# SparkFun_MicroMod_Function_SARA-R5.net
KiCad netlist of a schematic drawn in EAGLE
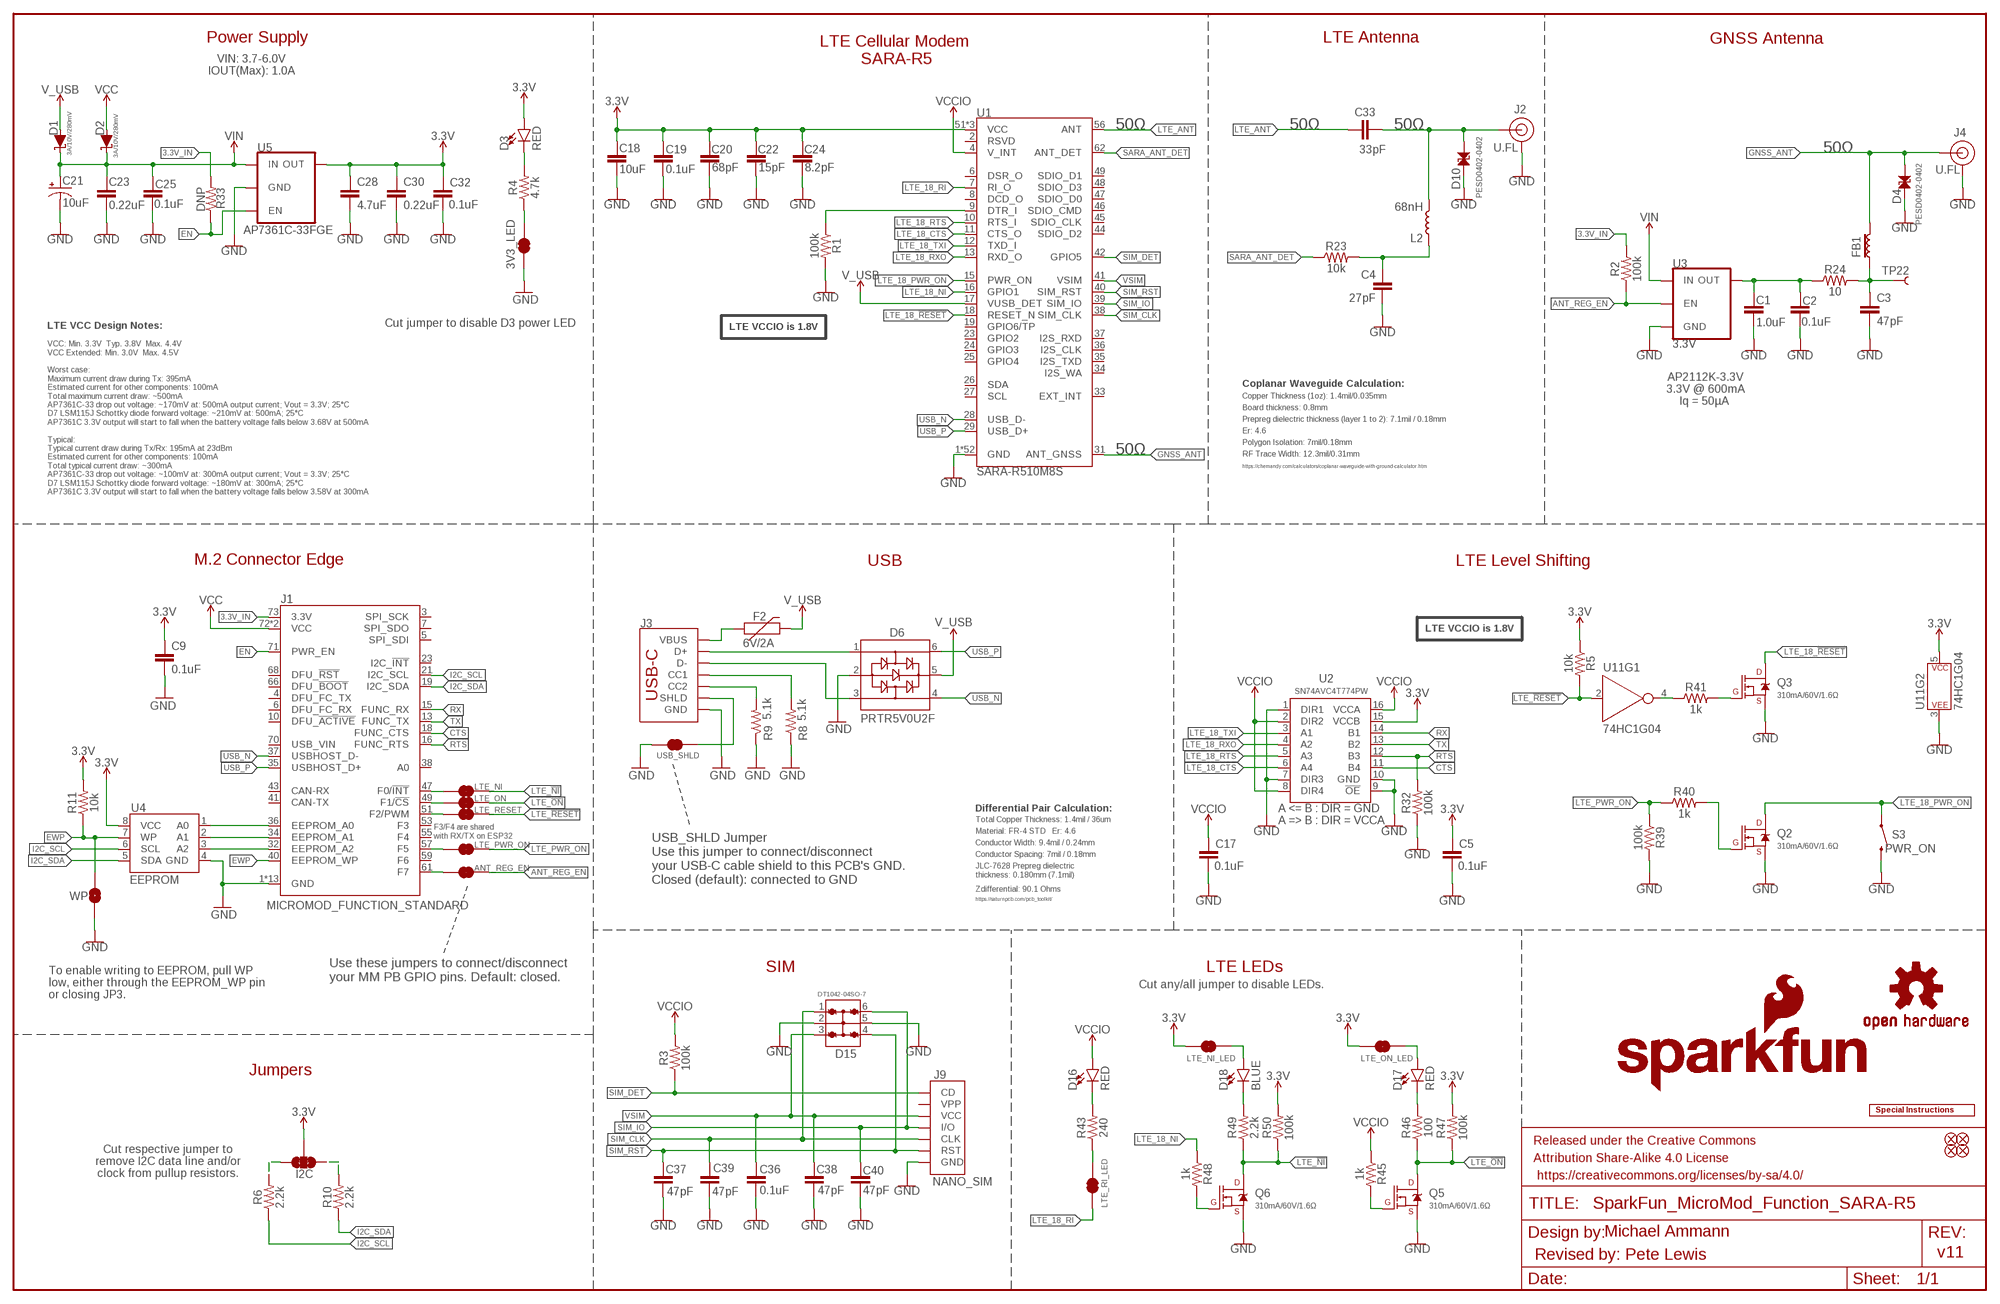
[diagram p0: schematic, sheet 1]

(export (version "E")
  (design (tool "Eeschema 10.0.6"))
  (components
    (comp (ref "3V3_LED")
      (value "JUMPER-SMT_2_NC_TRACE_SILK")
      (footprint "eagle-import:SMT-JUMPER_2_NC_TRACE_SILK")
      (libsource (lib "eagle-import") (part "JUMPER-SMT_2_NC_TRACE_SILK"))
    )
    (comp (ref "ANT_REG_EN")
      (value "JUMPER-SMT_2_NC_TRACE_SILK")
      (footprint "eagle-import:SMT-JUMPER_2_NC_TRACE_SILK")
      (libsource (lib "eagle-import") (part "JUMPER-SMT_2_NC_TRACE_SILK"))
    )
    (comp (ref "C1")
      (value "1.0uF")
      (footprint "eagle-import:0603")
      (libsource (lib "eagle-import") (part "1.0UF-0603-16V-10%"))
    )
    (comp (ref "C2")
      (value "0.1uF")
      (footprint "eagle-import:0402-TIGHT")
      (libsource (lib "eagle-import") (part "0.1UF-0402T-16V-10%"))
    )
    (comp (ref "C3")
      (value "47pF")
      (footprint "eagle-import:0603")
      (libsource (lib "eagle-import") (part "47PF-0603-50V-5%"))
    )
    (comp (ref "C4")
      (value "27pF")
      (footprint "eagle-import:0402")
      (libsource (lib "eagle-import") (part "27PF-0402-50V-5%"))
    )
    (comp (ref "C5")
      (value "0.1uF")
      (footprint "eagle-import:0402-TIGHT")
      (libsource (lib "eagle-import") (part "0.1UF-0402T-16V-10%"))
    )
    (comp (ref "C9")
      (value "0.1uF")
      (footprint "eagle-import:0402-TIGHT")
      (libsource (lib "eagle-import") (part "0.1UF-0402T-16V-10%"))
    )
    (comp (ref "C17")
      (value "0.1uF")
      (footprint "eagle-import:0402-TIGHT")
      (libsource (lib "eagle-import") (part "0.1UF-0402T-16V-10%"))
    )
    (comp (ref "C18")
      (value "10uF")
      (footprint "eagle-import:0603")
      (libsource (lib "eagle-import") (part "10UF-0603-6.3V-20%"))
    )
    (comp (ref "C19")
      (value "0.1uF")
      (footprint "eagle-import:0402-TIGHT")
      (libsource (lib "eagle-import") (part "0.1UF-0402T-16V-10%"))
    )
    (comp (ref "C20")
      (value "68pF")
      (footprint "eagle-import:0603")
      (libsource (lib "eagle-import") (part "68PF-0603-50V-5%"))
    )
    (comp (ref "C21")
      (value "10uF")
      (footprint "eagle-import:EIA3216")
      (libsource (lib "eagle-import") (part "10UF-POLAR-EIA3216-16V-10%(TANT)"))
    )
    (comp (ref "C22")
      (value "15pF")
      (footprint "eagle-import:0603")
      (libsource (lib "eagle-import") (part "15PF-0603-50V-5%"))
    )
    (comp (ref "C23")
      (value "0.22uF")
      (footprint "eagle-import:0603")
      (libsource (lib "eagle-import") (part "0.22UF-0603-25V-10%"))
    )
    (comp (ref "C24")
      (value "8.2pF")
      (footprint "eagle-import:0603")
      (fields (field (name "PROD_ID") "CAP-16662"))
      (libsource (lib "eagle-import") (part "8.2PF-0603-50V-10%"))
    )
    (comp (ref "C25")
      (value "0.1uF")
      (footprint "eagle-import:0402-TIGHT")
      (libsource (lib "eagle-import") (part "0.1UF-0402T-16V-10%"))
    )
    (comp (ref "C28")
      (value "4.7uF")
      (footprint "eagle-import:0603")
      (libsource (lib "eagle-import") (part "4.7UF-0603-6.3V-(10%)"))
    )
    (comp (ref "C30")
      (value "0.22uF")
      (footprint "eagle-import:0603")
      (libsource (lib "eagle-import") (part "0.22UF-0603-25V-10%"))
    )
    (comp (ref "C32")
      (value "0.1uF")
      (footprint "eagle-import:0402-TIGHT")
      (libsource (lib "eagle-import") (part "0.1UF-0402T-16V-10%"))
    )
    (comp (ref "C33")
      (value "33pF")
      (footprint "eagle-import:0402-TIGHT")
      (libsource (lib "eagle-import") (part "33PF-0402T-50V-5%"))
    )
    (comp (ref "C36")
      (value "0.1uF")
      (footprint "eagle-import:0402-TIGHT")
      (libsource (lib "eagle-import") (part "0.1UF-0402T-16V-10%"))
    )
    (comp (ref "C37")
      (value "47pF")
      (footprint "eagle-import:0603")
      (libsource (lib "eagle-import") (part "47PF-0603-50V-5%"))
    )
    (comp (ref "C38")
      (value "47pF")
      (footprint "eagle-import:0603")
      (libsource (lib "eagle-import") (part "47PF-0603-50V-5%"))
    )
    (comp (ref "C39")
      (value "47pF")
      (footprint "eagle-import:0603")
      (libsource (lib "eagle-import") (part "47PF-0603-50V-5%"))
    )
    (comp (ref "C40")
      (value "47pF")
      (footprint "eagle-import:0603")
      (libsource (lib "eagle-import") (part "47PF-0603-50V-5%"))
    )
    (comp (ref "D1")
      (value "3A/10V/280mV")
      (footprint "eagle-import:SOD-323")
      (libsource (lib "eagle-import") (part "DIODE-SCHOTTKY-BAT60A"))
    )
    (comp (ref "D2")
      (value "3A/10V/280mV")
      (footprint "eagle-import:SOD-323")
      (libsource (lib "eagle-import") (part "DIODE-SCHOTTKY-BAT60A"))
    )
    (comp (ref "D3")
      (value "RED")
      (footprint "eagle-import:LED-0603")
      (libsource (lib "eagle-import") (part "LED-RED_0603-KB"))
    )
    (comp (ref "D4")
      (value "PESD0402-0402")
      (footprint "eagle-import:0402")
      (fields
        (field (name "DIGIKEY_PART") "PESD0402-140CT-ND")
        (field (name "MOUSE_PART") "650-PESD0402-140")
      )
      (libsource (lib "eagle-import") (part "PESD0402-0402"))
    )
    (comp (ref "D6")
      (value "PRTR5V0U2F")
      (footprint "eagle-import:SOT886")
      (libsource (lib "eagle-import") (part "PRTR5V0U2F"))
    )
    (comp (ref "D10")
      (value "PESD0402-0402")
      (footprint "eagle-import:0402")
      (fields
        (field (name "DIGIKEY_PART") "PESD0402-140CT-ND")
        (field (name "MOUSE_PART") "650-PESD0402-140")
      )
      (libsource (lib "eagle-import") (part "PESD0402-0402"))
    )
    (comp (ref "D15")
      (value "DT1042-04SO-7")
      (footprint "eagle-import:SOT23-6L")
      (libsource (lib "eagle-import") (part "TVS_DIODE_ARRAY_4_ESDA6V1BC6"))
    )
    (comp (ref "D16")
      (value "RED")
      (footprint "eagle-import:LED-0603")
      (libsource (lib "eagle-import") (part "LED-RED_0603-KB"))
    )
    (comp (ref "D17")
      (value "RED")
      (footprint "eagle-import:LED-0603")
      (libsource (lib "eagle-import") (part "LED-RED_0603-KB"))
    )
    (comp (ref "D18")
      (value "BLUE")
      (footprint "eagle-import:LED-0603")
      (libsource (lib "eagle-import") (part "LED-BLUE0603"))
    )
    (comp (ref "F2")
      (value "6V/2A")
      (footprint "eagle-import:1210")
      (libsource (lib "eagle-import") (part "PPTC_6V2A"))
    )
    (comp (ref "FB1")
      (value "30Ω/1.8A")
      (footprint "eagle-import:0603")
      (libsource (lib "eagle-import") (part "FERRITE_BEAD-0603"))
    )
    (comp (ref "FD1")
      (value "FIDUCIALUFIDUCIAL")
      (footprint "eagle-import:FIDUCIAL-MICRO")
      (libsource (lib "eagle-import") (part "FIDUCIALUFIDUCIAL"))
    )
    (comp (ref "FD2")
      (value "FIDUCIALUFIDUCIAL")
      (footprint "eagle-import:FIDUCIAL-MICRO")
      (libsource (lib "eagle-import") (part "FIDUCIALUFIDUCIAL"))
    )
    (comp (ref "FD3")
      (value "FIDUCIALUFIDUCIAL")
      (footprint "eagle-import:FIDUCIAL-MICRO")
      (libsource (lib "eagle-import") (part "FIDUCIALUFIDUCIAL"))
    )
    (comp (ref "FD4")
      (value "FIDUCIALUFIDUCIAL")
      (footprint "eagle-import:FIDUCIAL-MICRO")
      (libsource (lib "eagle-import") (part "FIDUCIALUFIDUCIAL"))
    )
    (comp (ref "FRAME2")
      (value "FRAME-LEDGER")
      (footprint "eagle-import:CREATIVE_COMMONS")
      (libsource (lib "eagle-import") (part "FRAME-LEDGER"))
    )
    (comp (ref "I2C")
      (value "JUMPER-SMT_3_2-NC_TRACE_SILK")
      (footprint "eagle-import:SMT-JUMPER_3_2-NC_TRACE_SILK")
      (libsource (lib "eagle-import") (part "JUMPER-SMT_3_2-NC_TRACE_SILK"))
    )
    (comp (ref "J1")
      (value "MICROMOD_FUNCTION_STANDARD")
      (footprint "eagle-import:M.2-CARD-E-22_FUNCTION_STANDARD")
      (libsource (lib "eagle-import") (part "MICROMOD_FUNCTION_STANDARD"))
    )
    (comp (ref "J2")
      (value "U.FL")
      (footprint "eagle-import:U.FL")
      (libsource (lib "eagle-import") (part "U.FL2PIN"))
    )
    (comp (ref "J3")
      (value "USB_C_2-LAYER_PADS")
      (footprint "eagle-import:USB-C-16P-2LAYER-PADS")
      (libsource (lib "eagle-import") (part "USB_C_2-LAYER_PADS"))
    )
    (comp (ref "J4")
      (value "U.FL")
      (footprint "eagle-import:U.FL")
      (libsource (lib "eagle-import") (part "U.FL2PIN"))
    )
    (comp (ref "J9")
      (value "NANO_SIM")
      (footprint "eagle-import:NANO_SIM_PP")
      (libsource (lib "eagle-import") (part "SIMHOLDER_WITH_CD-PUSHPUSH"))
    )
    (comp (ref "L2")
      (value "68nH")
      (footprint "eagle-import:0402_COILCRAFT")
      (libsource (lib "eagle-import") (part "68NH-0402-200MA"))
    )
    (comp (ref "LOGO1")
      (value "SFE_LOGO_NAME_FLAME.2_INCH")
      (footprint "eagle-import:SFE_LOGO_NAME_FLAME_.2")
      (libsource (lib "eagle-import") (part "SFE_LOGO_NAME_FLAME.2_INCH"))
    )
    (comp (ref "LOGO2")
      (value "SFE_LOGO_FLAME.2_INCH")
      (footprint "eagle-import:SFE_LOGO_FLAME_.2")
      (libsource (lib "eagle-import") (part "SFE_LOGO_FLAME.2_INCH"))
    )
    (comp (ref "LOGO3")
      (value "SPECIAL_INSTRUCTIONS-ORDERING")
      (footprint "eagle-import:ORDERING_INSTRUCTIONS")
      (libsource (lib "eagle-import") (part "SPECIAL_INSTRUCTIONS-ORDERING"))
    )
    (comp (ref "LOGO4")
      (value "OSHW-LOGOMINI")
      (footprint "eagle-import:OSHW-LOGO-MINI")
      (libsource (lib "eagle-import") (part "OSHW-LOGOMINI"))
    )
    (comp (ref "LTE_NI")
      (value "JUMPER-SMT_2_NC_TRACE_SILK")
      (footprint "eagle-import:SMT-JUMPER_2_NC_TRACE_SILK")
      (libsource (lib "eagle-import") (part "JUMPER-SMT_2_NC_TRACE_SILK"))
    )
    (comp (ref "LTE_NI_LED")
      (value "JUMPER-SMT_2_NC_TRACE_SILK")
      (footprint "eagle-import:SMT-JUMPER_2_NC_TRACE_SILK")
      (libsource (lib "eagle-import") (part "JUMPER-SMT_2_NC_TRACE_SILK"))
    )
    (comp (ref "LTE_ON")
      (value "JUMPER-SMT_2_NC_TRACE_SILK")
      (footprint "eagle-import:SMT-JUMPER_2_NC_TRACE_SILK")
      (libsource (lib "eagle-import") (part "JUMPER-SMT_2_NC_TRACE_SILK"))
    )
    (comp (ref "LTE_ON_LED")
      (value "JUMPER-SMT_2_NC_TRACE_SILK")
      (footprint "eagle-import:SMT-JUMPER_2_NC_TRACE_SILK")
      (libsource (lib "eagle-import") (part "JUMPER-SMT_2_NC_TRACE_SILK"))
    )
    (comp (ref "LTE_PWR_ON")
      (value "JUMPER-SMT_2_NC_TRACE_SILK")
      (footprint "eagle-import:SMT-JUMPER_2_NC_TRACE_SILK")
      (libsource (lib "eagle-import") (part "JUMPER-SMT_2_NC_TRACE_SILK"))
    )
    (comp (ref "LTE_RESET")
      (value "JUMPER-SMT_2_NC_TRACE_SILK")
      (footprint "eagle-import:SMT-JUMPER_2_NC_TRACE_SILK")
      (libsource (lib "eagle-import") (part "JUMPER-SMT_2_NC_TRACE_SILK"))
    )
    (comp (ref "LTE_RI_LED")
      (value "JUMPER-SMT_2_NC_TRACE_SILK")
      (footprint "eagle-import:SMT-JUMPER_2_NC_TRACE_SILK")
      (libsource (lib "eagle-import") (part "JUMPER-SMT_2_NC_TRACE_SILK"))
    )
    (comp (ref "Q2")
      (value "310mA/60V/1.6Ω")
      (footprint "eagle-import:SOT323")
      (libsource (lib "eagle-import") (part "MOSFET-NCH-2N7002PW"))
    )
    (comp (ref "Q3")
      (value "310mA/60V/1.6Ω")
      (footprint "eagle-import:SOT323")
      (libsource (lib "eagle-import") (part "MOSFET-NCH-2N7002PW"))
    )
    (comp (ref "Q5")
      (value "310mA/60V/1.6Ω")
      (footprint "eagle-import:SOT323")
      (libsource (lib "eagle-import") (part "MOSFET-NCH-2N7002PW"))
    )
    (comp (ref "Q6")
      (value "310mA/60V/1.6Ω")
      (footprint "eagle-import:SOT323")
      (libsource (lib "eagle-import") (part "MOSFET-NCH-2N7002PW"))
    )
    (comp (ref "R1")
      (value "100k")
      (footprint "eagle-import:0402-TIGHT")
      (libsource (lib "eagle-import") (part "100KOHM-0402T-1/16W-1%"))
    )
    (comp (ref "R2")
      (value "100k")
      (footprint "eagle-import:0402-TIGHT")
      (libsource (lib "eagle-import") (part "100KOHM-0402T-1/16W-1%"))
    )
    (comp (ref "R3")
      (value "100k")
      (footprint "eagle-import:0402-TIGHT")
      (libsource (lib "eagle-import") (part "100KOHM-0402T-1/16W-1%"))
    )
    (comp (ref "R4")
      (value "4.7k")
      (footprint "eagle-import:0402-TIGHT")
      (libsource (lib "eagle-import") (part "4.7KOHM-0402T-1/16W-1%"))
    )
    (comp (ref "R5")
      (value "10k")
      (footprint "eagle-import:0402-TIGHT")
      (libsource (lib "eagle-import") (part "10KOHM-0402T-1/16W-1%"))
    )
    (comp (ref "R6")
      (value "2.2k")
      (footprint "eagle-import:0402-TIGHT")
      (libsource (lib "eagle-import") (part "2.2KOHM-0402T-1/16W-1%"))
    )
    (comp (ref "R8")
      (value "5.1k")
      (footprint "eagle-import:0402-TIGHT")
      (libsource (lib "eagle-import") (part "5.1KOHM-0402T-1/16W-1%"))
    )
    (comp (ref "R9")
      (value "5.1k")
      (footprint "eagle-import:0402-TIGHT")
      (libsource (lib "eagle-import") (part "5.1KOHM-0402T-1/16W-1%"))
    )
    (comp (ref "R10")
      (value "2.2k")
      (footprint "eagle-import:0402-TIGHT")
      (libsource (lib "eagle-import") (part "2.2KOHM-0402T-1/16W-1%"))
    )
    (comp (ref "R11")
      (value "10k")
      (footprint "eagle-import:0402-TIGHT")
      (libsource (lib "eagle-import") (part "10KOHM-0402T-1/16W-1%"))
    )
    (comp (ref "R23")
      (value "10k")
      (footprint "eagle-import:0402-TIGHT")
      (libsource (lib "eagle-import") (part "10KOHM-0402T-1/16W-1%"))
    )
    (comp (ref "R24")
      (value "10")
      (footprint "eagle-import:0603")
      (libsource (lib "eagle-import") (part "10OHM-0603-1/10W-1%"))
    )
    (comp (ref "R32")
      (value "100k")
      (footprint "eagle-import:0402-TIGHT")
      (libsource (lib "eagle-import") (part "100KOHM-0402T-1/16W-1%"))
    )
    (comp (ref "R33")
      (value "DNP")
      (footprint "eagle-import:0402-TIGHT")
      (libsource (lib "eagle-import") (part "100KOHM-0402T-1/16W-1%"))
    )
    (comp (ref "R39")
      (value "100k")
      (footprint "eagle-import:0402-TIGHT")
      (libsource (lib "eagle-import") (part "100KOHM-0402T-1/16W-1%"))
    )
    (comp (ref "R40")
      (value "1k")
      (footprint "eagle-import:0402-TIGHT")
      (libsource (lib "eagle-import") (part "1KOHM-0402T-1/16W-1%"))
    )
    (comp (ref "R41")
      (value "1k")
      (footprint "eagle-import:0402-TIGHT")
      (libsource (lib "eagle-import") (part "1KOHM-0402T-1/16W-1%"))
    )
    (comp (ref "R43")
      (value "240")
      (footprint "eagle-import:0603")
      (libsource (lib "eagle-import") (part "240OHM-0603-1/10W-1%"))
    )
    (comp (ref "R45")
      (value "1k")
      (footprint "eagle-import:0402-TIGHT")
      (libsource (lib "eagle-import") (part "1KOHM-0402T-1/16W-1%"))
    )
    (comp (ref "R46")
      (value "100")
      (footprint "eagle-import:0603")
      (libsource (lib "eagle-import") (part "100OHM-0603-1/10W-1%"))
    )
    (comp (ref "R47")
      (value "100k")
      (footprint "eagle-import:0402-TIGHT")
      (libsource (lib "eagle-import") (part "100KOHM-0402T-1/16W-1%"))
    )
    (comp (ref "R48")
      (value "1k")
      (footprint "eagle-import:0402-TIGHT")
      (libsource (lib "eagle-import") (part "1KOHM-0402T-1/16W-1%"))
    )
    (comp (ref "R49")
      (value "2.2k")
      (footprint "eagle-import:0402-TIGHT")
      (libsource (lib "eagle-import") (part "2.2KOHM-0402T-1/16W-1%"))
    )
    (comp (ref "R50")
      (value "100k")
      (footprint "eagle-import:0402-TIGHT")
      (libsource (lib "eagle-import") (part "100KOHM-0402T-1/16W-1%"))
    )
    (comp (ref "S3")
      (value "PWR_ON")
      (footprint "eagle-import:TACTILE_SWITCH_SMD_4.6X2.8MM")
      (libsource (lib "eagle-import") (part "MOMENTARY-SWITCH-SPST-SMD-4.6X2.8MM"))
    )
    (comp (ref "TP22")
      (value "TEST-POINT3X4")
      (footprint "eagle-import:PAD.03X.04")
      (libsource (lib "eagle-import") (part "TEST-POINT3X4"))
    )
    (comp (ref "U1")
      (value "SARA-R510M8S")
      (footprint "eagle-import:SARA-LGA")
      (libsource (lib "eagle-import") (part "SARA-R510M8S"))
    )
    (comp (ref "U2")
      (value "SN74AVC4T774PW")
      (footprint "eagle-import:SOP65P640X120-16N")
      (libsource (lib "eagle-import") (part "SN74AVC4T774PW"))
    )
    (comp (ref "U3")
      (value "3.3V")
      (footprint "eagle-import:SOT23-5")
      (libsource (lib "eagle-import") (part "V_REG_AP2112K-3.3V"))
    )
    (comp (ref "U4")
      (value "EEPROM")
      (footprint "eagle-import:SO08")
      (libsource (lib "eagle-import") (part "EEPROM-I2C512K"))
    )
    (comp (ref "U5")
      (value "AP7361C-33FGE")
      (footprint "eagle-import:UDFN-8")
      (libsource (lib "eagle-import") (part "AP7361C-33FGEUDFN-8"))
    )
    (comp (ref "U11")
      (value "74HC1G04")
      (footprint "eagle-import:SOT353")
      (libsource (lib "eagle-import") (part "741G04HC"))
    )
    (comp (ref "USB_SHLD")
      (value "JUMPER-SMT_2_NC_TRACE_SILK")
      (footprint "eagle-import:SMT-JUMPER_2_NC_TRACE_SILK")
      (libsource (lib "eagle-import") (part "JUMPER-SMT_2_NC_TRACE_SILK"))
    )
    (comp (ref "WP")
      (value "JUMPER-SMT_2_NO_SILK")
      (footprint "eagle-import:SMT-JUMPER_2_NO_SILK")
      (libsource (lib "eagle-import") (part "JUMPER-SMT_2_NO_SILK"))
    )
  )
  (nets
    (net (code "1") (name "/LTE_18_~{RESET}") (class "Default")
      (node (ref "Q3") (pin "3") (pinfunction "D_3") (pintype "bidirectional"))
      (node (ref "U1") (pin "18") (pinfunction "RESET_N_18") (pintype "input"))
    )
    (net (code "2") (name "/LTE_~{NI}") (class "Default")
      (node (ref "LTE_NI") (pin "1") (pinfunction "1_1") (pintype "passive"))
      (node (ref "Q6") (pin "3") (pinfunction "D_3") (pintype "bidirectional"))
      (node (ref "R49") (pin "1") (pinfunction "1_1") (pintype "passive"))
      (node (ref "R50") (pin "1") (pinfunction "1_1") (pintype "passive"))
    )
    (net (code "3") (name "/LTE_~{ON}") (class "Default")
      (node (ref "LTE_ON") (pin "1") (pinfunction "1_1") (pintype "passive"))
      (node (ref "Q5") (pin "3") (pinfunction "D_3") (pintype "bidirectional"))
      (node (ref "R46") (pin "1") (pinfunction "1_1") (pintype "passive"))
      (node (ref "R47") (pin "1") (pinfunction "1_1") (pintype "passive"))
    )
    (net (code "4") (name "/LTE_~{RESET}") (class "Default")
      (node (ref "LTE_RESET") (pin "1") (pinfunction "1_1") (pintype "passive"))
      (node (ref "R5") (pin "2") (pinfunction "2_2") (pintype "passive"))
      (node (ref "U11") (pin "2") (pinfunction "A_2") (pintype "bidirectional"))
    )
    (net (code "5") (name "3.3V") (class "Default")
      (node (ref "C18") (pin "1") (pinfunction "1_1") (pintype "passive"))
      (node (ref "C19") (pin "1") (pinfunction "1_1") (pintype "passive"))
      (node (ref "C20") (pin "1") (pinfunction "1_1") (pintype "passive"))
      (node (ref "C22") (pin "1") (pinfunction "1_1") (pintype "passive"))
      (node (ref "C24") (pin "1") (pinfunction "1_1") (pintype "passive"))
      (node (ref "C28") (pin "1") (pinfunction "1_1") (pintype "passive"))
      (node (ref "C30") (pin "1") (pinfunction "1_1") (pintype "passive"))
      (node (ref "C32") (pin "1") (pinfunction "1_1") (pintype "passive"))
      (node (ref "C5") (pin "1") (pinfunction "1_1") (pintype "passive"))
      (node (ref "C9") (pin "1") (pinfunction "1_1") (pintype "passive"))
      (node (ref "D3") (pin "A") (pinfunction "A_A") (pintype "passive"))
      (node (ref "I2C") (pin "2") (pinfunction "2_2") (pintype "passive"))
      (node (ref "LTE_NI_LED") (pin "2") (pinfunction "2_2") (pintype "passive"))
      (node (ref "LTE_ON_LED") (pin "2") (pinfunction "2_2") (pintype "passive"))
      (node (ref "R11") (pin "2") (pinfunction "2_2") (pintype "passive"))
      (node (ref "R47") (pin "2") (pinfunction "2_2") (pintype "passive"))
      (node (ref "R5") (pin "1") (pinfunction "1_1") (pintype "passive"))
      (node (ref "R50") (pin "2") (pinfunction "2_2") (pintype "passive"))
      (node (ref "U1") (pin "51") (pinfunction "VCC_51") (pintype "power_in"))
      (node (ref "U1") (pin "52") (pinfunction "VCC_52") (pintype "power_in"))
      (node (ref "U1") (pin "53") (pinfunction "VCC_53") (pintype "power_in"))
      (node (ref "U11") (pin "5") (pinfunction "P$V+_5") (pintype "bidirectional"))
      (node (ref "U2") (pin "15") (pinfunction "VCCB_15") (pintype "power_in"))
      (node (ref "U4") (pin "8") (pinfunction "VCC_8") (pintype "power_in"))
      (node (ref "U5") (pin "1") (pinfunction "OUT_1") (pintype "output"))
    )
    (net (code "6") (name "3.3V_IN") (class "Default")
      (node (ref "J1") (pin "73") (pinfunction "3.3V_73") (pintype "bidirectional"))
      (node (ref "R2") (pin "2") (pinfunction "2_2") (pintype "passive"))
      (node (ref "R33") (pin "2") (pinfunction "2_2") (pintype "passive"))
    )
    (net (code "7") (name "ANT_REG_EN") (class "Default")
      (node (ref "ANT_REG_EN") (pin "1") (pinfunction "1_1") (pintype "passive"))
      (node (ref "R2") (pin "1") (pinfunction "1_1") (pintype "passive"))
      (node (ref "U3") (pin "3") (pinfunction "EN_3") (pintype "input"))
    )
    (net (code "8") (name "CTS") (class "Default")
      (node (ref "J1") (pin "18") (pinfunction "FUNC_CTS_18") (pintype "bidirectional"))
      (node (ref "U2") (pin "11") (pinfunction "B4_11") (pintype "bidirectional"))
    )
    (net (code "9") (name "EN") (class "Default")
      (node (ref "J1") (pin "71") (pinfunction "PWR_EN_71") (pintype "bidirectional"))
      (node (ref "R33") (pin "1") (pinfunction "1_1") (pintype "passive"))
      (node (ref "U5") (pin "5") (pinfunction "EN_5") (pintype "bidirectional"))
    )
    (net (code "10") (name "EWP") (class "Default")
      (node (ref "J1") (pin "40") (pinfunction "EEPROM_WP_40") (pintype "bidirectional"))
      (node (ref "R11") (pin "1") (pinfunction "1_1") (pintype "passive"))
      (node (ref "U4") (pin "7") (pinfunction "WP_7") (pintype "bidirectional"))
      (node (ref "WP") (pin "2") (pinfunction "2_2") (pintype "passive"))
    )
    (net (code "11") (name "GND") (class "Default")
      (node (ref "3V3_LED") (pin "1") (pinfunction "1_1") (pintype "passive"))
      (node (ref "C1") (pin "2") (pinfunction "2_2") (pintype "passive"))
      (node (ref "C17") (pin "2") (pinfunction "2_2") (pintype "passive"))
      (node (ref "C18") (pin "2") (pinfunction "2_2") (pintype "passive"))
      (node (ref "C19") (pin "2") (pinfunction "2_2") (pintype "passive"))
      (node (ref "C2") (pin "2") (pinfunction "2_2") (pintype "passive"))
      (node (ref "C20") (pin "2") (pinfunction "2_2") (pintype "passive"))
      (node (ref "C21") (pin "-") (pinfunction "-_-") (pintype "passive"))
      (node (ref "C22") (pin "2") (pinfunction "2_2") (pintype "passive"))
      (node (ref "C23") (pin "2") (pinfunction "2_2") (pintype "passive"))
      (node (ref "C24") (pin "2") (pinfunction "2_2") (pintype "passive"))
      (node (ref "C25") (pin "2") (pinfunction "2_2") (pintype "passive"))
      (node (ref "C28") (pin "2") (pinfunction "2_2") (pintype "passive"))
      (node (ref "C3") (pin "2") (pinfunction "2_2") (pintype "passive"))
      (node (ref "C30") (pin "2") (pinfunction "2_2") (pintype "passive"))
      (node (ref "C32") (pin "2") (pinfunction "2_2") (pintype "passive"))
      (node (ref "C36") (pin "1") (pinfunction "1_1") (pintype "passive"))
      (node (ref "C37") (pin "2") (pinfunction "2_2") (pintype "passive"))
      (node (ref "C38") (pin "1") (pinfunction "1_1") (pintype "passive"))
      (node (ref "C39") (pin "2") (pinfunction "2_2") (pintype "passive"))
      (node (ref "C4") (pin "2") (pinfunction "2_2") (pintype "passive"))
      (node (ref "C40") (pin "1") (pinfunction "1_1") (pintype "passive"))
      (node (ref "C5") (pin "2") (pinfunction "2_2") (pintype "passive"))
      (node (ref "C9") (pin "2") (pinfunction "2_2") (pintype "passive"))
      (node (ref "D10") (pin "2") (pinfunction "2_2") (pintype "bidirectional"))
      (node (ref "D15") (pin "2") (pinfunction "2_2") (pintype "bidirectional"))
      (node (ref "D15") (pin "5") (pinfunction "5_5") (pintype "bidirectional"))
      (node (ref "D4") (pin "2") (pinfunction "2_2") (pintype "bidirectional"))
      (node (ref "D6") (pin "2") (pinfunction "2_2") (pintype "power_in"))
      (node (ref "J1") (pin "1") (pinfunction "GND_1") (pintype "bidirectional"))
      (node (ref "J1") (pin "2") (pinfunction "GND_2") (pintype "bidirectional"))
      (node (ref "J1") (pin "33") (pinfunction "GND_33") (pintype "bidirectional"))
      (node (ref "J1") (pin "39") (pinfunction "GND_39") (pintype "bidirectional"))
      (node (ref "J1") (pin "45") (pinfunction "GND_45") (pintype "bidirectional"))
      (node (ref "J1") (pin "75") (pinfunction "GND_75") (pintype "bidirectional"))
      (node (ref "J1") (pin "8") (pinfunction "GND_8") (pintype "bidirectional"))
      (node (ref "J1") (pin "GND1") (pinfunction "GND_GND1") (pintype "bidirectional"))
      (node (ref "J1") (pin "GND2") (pinfunction "GND_GND2") (pintype "bidirectional"))
      (node (ref "J1") (pin "GND3") (pinfunction "GND_GND3") (pintype "bidirectional"))
      (node (ref "J1") (pin "GND4") (pinfunction "GND_GND4") (pintype "bidirectional"))
      (node (ref "J1") (pin "GND5") (pinfunction "GND_GND5") (pintype "bidirectional"))
      (node (ref "J1") (pin "GND6") (pinfunction "GND_GND6") (pintype "bidirectional"))
      (node (ref "J2") (pin "1") (pinfunction "GND_1") (pintype "bidirectional"))
      (node (ref "J2") (pin "2") (pinfunction "GND_2") (pintype "bidirectional"))
      (node (ref "J3") (pin "GND") (pinfunction "GND_GND") (pintype "bidirectional"))
      (node (ref "J3") (pin "GND2") (pinfunction "GND_GND2") (pintype "bidirectional"))
      (node (ref "J4") (pin "1") (pinfunction "GND_1") (pintype "bidirectional"))
      (node (ref "J4") (pin "2") (pinfunction "GND_2") (pintype "bidirectional"))
      (node (ref "J9") (pin "A1") (pinfunction "GND_A1") (pintype "power_in"))
      (node (ref "J9") (pin "A2") (pinfunction "GND_A2") (pintype "power_in"))
      (node (ref "J9") (pin "A3") (pinfunction "GND_A3") (pintype "power_in"))
      (node (ref "J9") (pin "A4") (pinfunction "GND_A4") (pintype "power_in"))
      (node (ref "J9") (pin "C5") (pinfunction "GND_C5") (pintype "power_in"))
      (node (ref "Q2") (pin "2") (pinfunction "S_2") (pintype "bidirectional"))
      (node (ref "Q3") (pin "2") (pinfunction "S_2") (pintype "bidirectional"))
      (node (ref "Q5") (pin "2") (pinfunction "S_2") (pintype "bidirectional"))
      (node (ref "Q6") (pin "2") (pinfunction "S_2") (pintype "bidirectional"))
      (node (ref "R1") (pin "2") (pinfunction "2_2") (pintype "passive"))
      (node (ref "R32") (pin "1") (pinfunction "1_1") (pintype "passive"))
      (node (ref "R39") (pin "2") (pinfunction "2_2") (pintype "passive"))
      (node (ref "R8") (pin "1") (pinfunction "1_1") (pintype "passive"))
      (node (ref "R9") (pin "1") (pinfunction "1_1") (pintype "passive"))
      (node (ref "S3") (pin "3") (pinfunction "2_3") (pintype "passive"))
      (node (ref "S3") (pin "4") (pinfunction "2_4") (pintype "passive"))
      (node (ref "U1") (pin "1") (pinfunction "GND_1") (pintype "power_in"))
      (node (ref "U1") (pin "14") (pinfunction "GND_14") (pintype "power_in"))
      (node (ref "U1") (pin "20") (pinfunction "GND_20") (pintype "power_in"))
      (node (ref "U1") (pin "21") (pinfunction "GND_21") (pintype "power_in"))
      (node (ref "U1") (pin "22") (pinfunction "GND_22") (pintype "power_in"))
      (node (ref "U1") (pin "3") (pinfunction "GND_3") (pintype "power_in"))
      (node (ref "U1") (pin "30") (pinfunction "GND_30") (pintype "power_in"))
      (node (ref "U1") (pin "32") (pinfunction "GND_32") (pintype "power_in"))
      (node (ref "U1") (pin "43") (pinfunction "GND_43") (pintype "power_in"))
      (node (ref "U1") (pin "5") (pinfunction "GND_5") (pintype "power_in"))
      (node (ref "U1") (pin "50") (pinfunction "GND_50") (pintype "power_in"))
      (node (ref "U1") (pin "54") (pinfunction "GND_54") (pintype "power_in"))
      (node (ref "U1") (pin "55") (pinfunction "GND_55") (pintype "power_in"))
      (node (ref "U1") (pin "57") (pinfunction "GND_57") (pintype "power_in"))
      (node (ref "U1") (pin "58") (pinfunction "GND_58") (pintype "power_in"))
      (node (ref "U1") (pin "59") (pinfunction "GND_59") (pintype "power_in"))
      (node (ref "U1") (pin "60") (pinfunction "GND_60") (pintype "power_in"))
      (node (ref "U1") (pin "61") (pinfunction "GND_61") (pintype "power_in"))
      (node (ref "U1") (pin "63") (pinfunction "GND_63") (pintype "power_in"))
      (node (ref "U1") (pin "64") (pinfunction "GND_64") (pintype "power_in"))
      (node (ref "U1") (pin "65") (pinfunction "GND_65") (pintype "power_in"))
      (node (ref "U1") (pin "66") (pinfunction "GND_66") (pintype "power_in"))
      (node (ref "U1") (pin "67") (pinfunction "GND_67") (pintype "power_in"))
      (node (ref "U1") (pin "68") (pinfunction "GND_68") (pintype "power_in"))
      (node (ref "U1") (pin "69") (pinfunction "GND_69") (pintype "power_in"))
      (node (ref "U1") (pin "70") (pinfunction "GND_70") (pintype "power_in"))
      (node (ref "U1") (pin "71") (pinfunction "GND_71") (pintype "power_in"))
      (node (ref "U1") (pin "72") (pinfunction "GND_72") (pintype "power_in"))
      (node (ref "U1") (pin "73") (pinfunction "GND_73") (pintype "power_in"))
      (node (ref "U1") (pin "74") (pinfunction "GND_74") (pintype "power_in"))
      (node (ref "U1") (pin "75") (pinfunction "GND_75") (pintype "power_in"))
      (node (ref "U1") (pin "76") (pinfunction "GND_76") (pintype "power_in"))
      (node (ref "U1") (pin "77") (pinfunction "GND_77") (pintype "power_in"))
      (node (ref "U1") (pin "78") (pinfunction "GND_78") (pintype "power_in"))
      (node (ref "U1") (pin "79") (pinfunction "GND_79") (pintype "power_in"))
      (node (ref "U1") (pin "80") (pinfunction "GND_80") (pintype "power_in"))
      (node (ref "U1") (pin "81") (pinfunction "GND_81") (pintype "power_in"))
      (node (ref "U1") (pin "82") (pinfunction "GND_82") (pintype "power_in"))
      (node (ref "U1") (pin "83") (pinfunction "GND_83") (pintype "power_in"))
      (node (ref "U1") (pin "84") (pinfunction "GND_84") (pintype "power_in"))
      (node (ref "U1") (pin "85") (pinfunction "GND_85") (pintype "power_in"))
      (node (ref "U1") (pin "86") (pinfunction "GND_86") (pintype "power_in"))
      (node (ref "U1") (pin "87") (pinfunction "GND_87") (pintype "power_in"))
      (node (ref "U1") (pin "88") (pinfunction "GND_88") (pintype "power_in"))
      (node (ref "U1") (pin "89") (pinfunction "GND_89") (pintype "power_in"))
      (node (ref "U1") (pin "90") (pinfunction "GND_90") (pintype "power_in"))
      (node (ref "U1") (pin "91") (pinfunction "GND_91") (pintype "power_in"))
      (node (ref "U1") (pin "92") (pinfunction "GND_92") (pintype "power_in"))
      (node (ref "U1") (pin "93") (pinfunction "GND_93") (pintype "power_in"))
      (node (ref "U1") (pin "94") (pinfunction "GND_94") (pintype "power_in"))
      (node (ref "U1") (pin "95") (pinfunction "GND_95") (pintype "power_in"))
      (node (ref "U1") (pin "96") (pinfunction "GND_96") (pintype "power_in"))
      (node (ref "U11") (pin "3") (pinfunction "P$V-_3") (pintype "bidirectional"))
      (node (ref "U2") (pin "1") (pinfunction "DIR1_1") (pintype "input"))
      (node (ref "U2") (pin "10") (pinfunction "GND_10") (pintype "power_in"))
      (node (ref "U2") (pin "7") (pinfunction "DIR3_7") (pintype "input"))
      (node (ref "U2") (pin "9") (pinfunction "~{OE}_9") (pintype "input"))
      (node (ref "U3") (pin "2") (pinfunction "GND_2") (pintype "input"))
      (node (ref "U4") (pin "4") (pinfunction "GND_4") (pintype "power_in"))
      (node (ref "U5") (pin "4") (pinfunction "GND_4") (pintype "input"))
      (node (ref "U5") (pin "EP") (pinfunction "GND_EP") (pintype "input"))
      (node (ref "USB_SHLD") (pin "2") (pinfunction "2_2") (pintype "passive"))
      (node (ref "WP") (pin "1") (pinfunction "1_1") (pintype "passive"))
    )
    (net (code "12") (name "GNSS_ANT") (class "Default")
      (node (ref "D4") (pin "1") (pinfunction "1_1") (pintype "bidirectional"))
      (node (ref "FB1") (pin "2") (pinfunction "2_2") (pintype "passive"))
      (node (ref "J4") (pin "FEED") (pinfunction "SIGNAL_FEED") (pintype "bidirectional"))
      (node (ref "U1") (pin "31") (pinfunction "ANT_GNSS_31") (pintype "input"))
    )
    (net (code "13") (name "I2C_SCL") (class "Default")
      (node (ref "J1") (pin "21") (pinfunction "I2C_SCL_21") (pintype "bidirectional"))
      (node (ref "R6") (pin "1") (pinfunction "1_1") (pintype "passive"))
      (node (ref "U4") (pin "6") (pinfunction "SCL_6") (pintype "bidirectional"))
    )
    (net (code "14") (name "I2C_SDA") (class "Default")
      (node (ref "J1") (pin "19") (pinfunction "I2C_SDA_19") (pintype "bidirectional"))
      (node (ref "R10") (pin "1") (pinfunction "1_1") (pintype "passive"))
      (node (ref "U4") (pin "5") (pinfunction "SDA_5") (pintype "bidirectional"))
    )
    (net (code "15") (name "LTE_18_CTS") (class "Default")
      (node (ref "U1") (pin "11") (pinfunction "CTS_O_11") (pintype "output"))
      (node (ref "U2") (pin "6") (pinfunction "A4_6") (pintype "bidirectional"))
    )
    (net (code "16") (name "LTE_18_NI") (class "Default")
      (node (ref "R48") (pin "1") (pinfunction "1_1") (pintype "passive"))
      (node (ref "U1") (pin "16") (pinfunction "GPIO1_16") (pintype "bidirectional"))
    )
    (net (code "17") (name "LTE_18_PWR_ON") (class "Default")
      (node (ref "Q2") (pin "3") (pinfunction "D_3") (pintype "bidirectional"))
      (node (ref "S3") (pin "1") (pinfunction "1_1") (pintype "passive"))
      (node (ref "S3") (pin "2") (pinfunction "1_2") (pintype "passive"))
      (node (ref "U1") (pin "15") (pinfunction "PWR_ON_15") (pintype "input"))
    )
    (net (code "18") (name "LTE_18_RI") (class "Default")
      (node (ref "LTE_RI_LED") (pin "2") (pinfunction "2_2") (pintype "passive"))
      (node (ref "U1") (pin "7") (pinfunction "RI_O_7") (pintype "output"))
    )
    (net (code "19") (name "LTE_18_RTS") (class "Default")
      (node (ref "U1") (pin "10") (pinfunction "RTS_I_10") (pintype "input"))
      (node (ref "U2") (pin "5") (pinfunction "A3_5") (pintype "bidirectional"))
    )
    (net (code "20") (name "LTE_18_RXO") (class "Default")
      (node (ref "U1") (pin "13") (pinfunction "RXD_O_13") (pintype "output"))
      (node (ref "U2") (pin "4") (pinfunction "A2_4") (pintype "bidirectional"))
    )
    (net (code "21") (name "LTE_18_TXI") (class "Default")
      (node (ref "U1") (pin "12") (pinfunction "TXD_I_12") (pintype "input"))
      (node (ref "U2") (pin "3") (pinfunction "A1_3") (pintype "bidirectional"))
    )
    (net (code "22") (name "LTE_ANT") (class "Default")
      (node (ref "C33") (pin "1") (pinfunction "1_1") (pintype "passive"))
      (node (ref "U1") (pin "56") (pinfunction "ANT_56") (pintype "bidirectional"))
    )
    (net (code "23") (name "LTE_PWR_ON") (class "Default")
      (node (ref "LTE_PWR_ON") (pin "1") (pinfunction "1_1") (pintype "passive"))
      (node (ref "R39") (pin "1") (pinfunction "1_1") (pintype "passive"))
      (node (ref "R40") (pin "1") (pinfunction "1_1") (pintype "passive"))
    )
    (net (code "24") (name "Net-(3V3_LED-Pad2)") (class "Default")
      (node (ref "3V3_LED") (pin "2") (pinfunction "2_2") (pintype "passive"))
      (node (ref "R4") (pin "1") (pinfunction "1_1") (pintype "passive"))
    )
    (net (code "25") (name "Net-(C3-Pad1)") (class "Default")
      (node (ref "C3") (pin "1") (pinfunction "1_1") (pintype "passive"))
      (node (ref "FB1") (pin "1") (pinfunction "1_1") (pintype "passive"))
      (node (ref "R24") (pin "2") (pinfunction "2_2") (pintype "passive"))
      (node (ref "TP22") (pin "1") (pinfunction "1_1") (pintype "bidirectional"))
    )
    (net (code "26") (name "Net-(D3-PadC)") (class "Default")
      (node (ref "D3") (pin "C") (pinfunction "C_C") (pintype "passive"))
      (node (ref "R4") (pin "2") (pinfunction "2_2") (pintype "passive"))
    )
    (net (code "27") (name "Net-(D6-Pad1)") (class "Default")
      (node (ref "D6") (pin "1") (pinfunction "1_1") (pintype "bidirectional"))
      (node (ref "J3") (pin "A6") (pinfunction "D+_A6") (pintype "bidirectional"))
      (node (ref "J3") (pin "B6") (pinfunction "D+_B6") (pintype "bidirectional"))
    )
    (net (code "28") (name "Net-(D6-Pad3)") (class "Default")
      (node (ref "D6") (pin "3") (pinfunction "3_3") (pintype "bidirectional"))
      (node (ref "J3") (pin "A7") (pinfunction "D-_A7") (pintype "bidirectional"))
      (node (ref "J3") (pin "B7") (pinfunction "D-_B7") (pintype "bidirectional"))
    )
    (net (code "29") (name "Net-(D16-PadC)") (class "Default")
      (node (ref "D16") (pin "C") (pinfunction "C_C") (pintype "passive"))
      (node (ref "R43") (pin "2") (pinfunction "2_2") (pintype "passive"))
    )
    (net (code "30") (name "Net-(D17-PadA)") (class "Default")
      (node (ref "D17") (pin "A") (pinfunction "A_A") (pintype "passive"))
      (node (ref "LTE_ON_LED") (pin "1") (pinfunction "1_1") (pintype "passive"))
    )
    (net (code "31") (name "Net-(D17-PadC)") (class "Default")
      (node (ref "D17") (pin "C") (pinfunction "C_C") (pintype "passive"))
      (node (ref "R46") (pin "2") (pinfunction "2_2") (pintype "passive"))
    )
    (net (code "32") (name "Net-(D18-PadA)") (class "Default")
      (node (ref "D18") (pin "A") (pinfunction "A_A") (pintype "passive"))
      (node (ref "LTE_NI_LED") (pin "1") (pinfunction "1_1") (pintype "passive"))
    )
    (net (code "33") (name "Net-(D18-PadC)") (class "Default")
      (node (ref "D18") (pin "C") (pinfunction "C_C") (pintype "passive"))
      (node (ref "R49") (pin "2") (pinfunction "2_2") (pintype "passive"))
    )
    (net (code "34") (name "Net-(F2-Pad1)") (class "Default")
      (node (ref "F2") (pin "1") (pinfunction "1_1") (pintype "bidirectional"))
      (node (ref "J3") (pin "VBUS1") (pinfunction "VBUS_VBUS1") (pintype "bidirectional"))
      (node (ref "J3") (pin "VBUS2") (pinfunction "VBUS_VBUS2") (pintype "bidirectional"))
    )
    (net (code "35") (name "Net-(I2C-Pad1)") (class "Default")
      (node (ref "I2C") (pin "1") (pinfunction "1_1") (pintype "passive"))
      (node (ref "R10") (pin "2") (pinfunction "2_2") (pintype "passive"))
    )
    (net (code "36") (name "Net-(I2C-Pad3)") (class "Default")
      (node (ref "I2C") (pin "3") (pinfunction "3_3") (pintype "passive"))
      (node (ref "R6") (pin "2") (pinfunction "2_2") (pintype "passive"))
    )
    (net (code "37") (name "Net-(J1-EEPROM_A0)") (class "Default")
      (node (ref "J1") (pin "36") (pinfunction "EEPROM_A0_36") (pintype "bidirectional"))
      (node (ref "U4") (pin "1") (pinfunction "A0_1") (pintype "bidirectional"))
    )
    (net (code "38") (name "Net-(J1-EEPROM_A1)") (class "Default")
      (node (ref "J1") (pin "34") (pinfunction "EEPROM_A1_34") (pintype "bidirectional"))
      (node (ref "U4") (pin "2") (pinfunction "A1_2") (pintype "bidirectional"))
    )
    (net (code "39") (name "Net-(J1-EEPROM_A2)") (class "Default")
      (node (ref "J1") (pin "32") (pinfunction "EEPROM_A2_32") (pintype "bidirectional"))
      (node (ref "U4") (pin "3") (pinfunction "A2_3") (pintype "bidirectional"))
    )
    (net (code "40") (name "Net-(J1-F0{slash}~{INT})") (class "Default")
      (node (ref "J1") (pin "47") (pinfunction "F0/~{INT}_47") (pintype "bidirectional"))
      (node (ref "LTE_NI") (pin "2") (pinfunction "2_2") (pintype "passive"))
    )
    (net (code "41") (name "Net-(J1-F1{slash}~{CS})") (class "Default")
      (node (ref "J1") (pin "49") (pinfunction "F1/~{CS}_49") (pintype "bidirectional"))
      (node (ref "LTE_ON") (pin "2") (pinfunction "2_2") (pintype "passive"))
    )
    (net (code "42") (name "Net-(J1-F2{slash}PWM)") (class "Default")
      (node (ref "J1") (pin "51") (pinfunction "F2/PWM_51") (pintype "bidirectional"))
      (node (ref "LTE_RESET") (pin "2") (pinfunction "2_2") (pintype "passive"))
    )
    (net (code "43") (name "Net-(J1-F5)") (class "Default")
      (node (ref "J1") (pin "57") (pinfunction "F5_57") (pintype "bidirectional"))
      (node (ref "LTE_PWR_ON") (pin "2") (pinfunction "2_2") (pintype "passive"))
    )
    (net (code "44") (name "Net-(J1-F7)") (class "Default")
      (node (ref "ANT_REG_EN") (pin "2") (pinfunction "2_2") (pintype "passive"))
      (node (ref "J1") (pin "61") (pinfunction "F7_61") (pintype "bidirectional"))
    )
    (net (code "45") (name "Net-(J2-SIGNAL)") (class "Default")
      (node (ref "C33") (pin "2") (pinfunction "2_2") (pintype "passive"))
      (node (ref "D10") (pin "1") (pinfunction "1_1") (pintype "bidirectional"))
      (node (ref "J2") (pin "FEED") (pinfunction "SIGNAL_FEED") (pintype "bidirectional"))
      (node (ref "L2") (pin "P$2") (pinfunction "2_P$2") (pintype "passive"))
    )
    (net (code "46") (name "Net-(J3-CC1)") (class "Default")
      (node (ref "J3") (pin "A5") (pinfunction "CC1_A5") (pintype "bidirectional"))
      (node (ref "R8") (pin "2") (pinfunction "2_2") (pintype "passive"))
    )
    (net (code "47") (name "Net-(J3-CC2)") (class "Default")
      (node (ref "J3") (pin "B5") (pinfunction "CC2_B5") (pintype "bidirectional"))
      (node (ref "R9") (pin "2") (pinfunction "2_2") (pintype "passive"))
    )
    (net (code "48") (name "Net-(J3-SHLD-PadSHLD1)") (class "Default")
      (node (ref "J3") (pin "SHLD1") (pinfunction "SHLD_SHLD1") (pintype "bidirectional"))
      (node (ref "J3") (pin "SHLD2") (pinfunction "SHLD_SHLD2") (pintype "bidirectional"))
      (node (ref "J3") (pin "SHLD3") (pinfunction "SHLD_SHLD3") (pintype "bidirectional"))
      (node (ref "J3") (pin "SHLD4") (pinfunction "SHLD_SHLD4") (pintype "bidirectional"))
      (node (ref "USB_SHLD") (pin "1") (pinfunction "1_1") (pintype "passive"))
    )
    (net (code "49") (name "Net-(L2-1)") (class "Default")
      (node (ref "C4") (pin "1") (pinfunction "1_1") (pintype "passive"))
      (node (ref "L2") (pin "P$1") (pinfunction "1_P$1") (pintype "passive"))
      (node (ref "R23") (pin "2") (pinfunction "2_2") (pintype "passive"))
    )
    (net (code "50") (name "Net-(LTE_RI_LED-Pad1)") (class "Default")
      (node (ref "LTE_RI_LED") (pin "1") (pinfunction "1_1") (pintype "passive"))
      (node (ref "R43") (pin "1") (pinfunction "1_1") (pintype "passive"))
    )
    (net (code "51") (name "Net-(Q2-G)") (class "Default")
      (node (ref "Q2") (pin "1") (pinfunction "G_1") (pintype "bidirectional"))
      (node (ref "R40") (pin "2") (pinfunction "2_2") (pintype "passive"))
    )
    (net (code "52") (name "Net-(Q3-G)") (class "Default")
      (node (ref "Q3") (pin "1") (pinfunction "G_1") (pintype "bidirectional"))
      (node (ref "R41") (pin "2") (pinfunction "2_2") (pintype "passive"))
    )
    (net (code "53") (name "Net-(Q5-G)") (class "Default")
      (node (ref "Q5") (pin "1") (pinfunction "G_1") (pintype "bidirectional"))
      (node (ref "R45") (pin "2") (pinfunction "2_2") (pintype "passive"))
    )
    (net (code "54") (name "Net-(Q6-G)") (class "Default")
      (node (ref "Q6") (pin "1") (pinfunction "G_1") (pintype "bidirectional"))
      (node (ref "R48") (pin "2") (pinfunction "2_2") (pintype "passive"))
    )
    (net (code "55") (name "Net-(U1-DTR_I)") (class "Default")
      (node (ref "R1") (pin "1") (pinfunction "1_1") (pintype "passive"))
      (node (ref "U1") (pin "9") (pinfunction "DTR_I_9") (pintype "input"))
    )
    (net (code "56") (name "Net-(U3-OUT)") (class "Default")
      (node (ref "C1") (pin "1") (pinfunction "1_1") (pintype "passive"))
      (node (ref "C2") (pin "1") (pinfunction "1_1") (pintype "passive"))
      (node (ref "R24") (pin "1") (pinfunction "1_1") (pintype "passive"))
      (node (ref "U3") (pin "5") (pinfunction "OUT_5") (pintype "passive"))
    )
    (net (code "57") (name "Net-(U11A-Y)") (class "Default")
      (node (ref "R41") (pin "1") (pinfunction "1_1") (pintype "passive"))
      (node (ref "U11") (pin "4") (pinfunction "Y_4") (pintype "bidirectional"))
    )
    (net (code "58") (name "RTS") (class "Default")
      (node (ref "J1") (pin "16") (pinfunction "FUNC_RTS_16") (pintype "bidirectional"))
      (node (ref "R32") (pin "2") (pinfunction "2_2") (pintype "passive"))
      (node (ref "U2") (pin "12") (pinfunction "B3_12") (pintype "bidirectional"))
    )
    (net (code "59") (name "RX") (class "Default")
      (node (ref "J1") (pin "15") (pinfunction "FUNC_RX_15") (pintype "bidirectional"))
      (node (ref "U2") (pin "14") (pinfunction "B1_14") (pintype "bidirectional"))
    )
    (net (code "60") (name "SARA_ANT_DET") (class "Default")
      (node (ref "R23") (pin "1") (pinfunction "1_1") (pintype "passive"))
      (node (ref "U1") (pin "62") (pinfunction "ANT_DET_62") (pintype "input"))
    )
    (net (code "61") (name "SIM_CLK") (class "Default")
      (node (ref "C39") (pin "1") (pinfunction "1_1") (pintype "passive"))
      (node (ref "D15") (pin "1") (pinfunction "1_1") (pintype "bidirectional"))
      (node (ref "J9") (pin "C3") (pinfunction "CLK_C3") (pintype "input"))
      (node (ref "U1") (pin "38") (pinfunction "SIM_CLK_38") (pintype "output"))
    )
    (net (code "62") (name "SIM_DET") (class "Default")
      (node (ref "J9") (pin "CD") (pinfunction "CD_CD") (pintype "input"))
      (node (ref "R3") (pin "1") (pinfunction "1_1") (pintype "passive"))
      (node (ref "U1") (pin "42") (pinfunction "GPIO5_42") (pintype "bidirectional"))
    )
    (net (code "63") (name "SIM_IO") (class "Default")
      (node (ref "C40") (pin "2") (pinfunction "2_2") (pintype "passive"))
      (node (ref "D15") (pin "6") (pinfunction "6_6") (pintype "bidirectional"))
      (node (ref "J9") (pin "C7") (pinfunction "I/O_C7") (pintype "bidirectional"))
      (node (ref "U1") (pin "39") (pinfunction "SIM_IO_39") (pintype "bidirectional"))
    )
    (net (code "64") (name "SIM_RST") (class "Default")
      (node (ref "C37") (pin "1") (pinfunction "1_1") (pintype "passive"))
      (node (ref "D15") (pin "4") (pinfunction "4_4") (pintype "bidirectional"))
      (node (ref "J9") (pin "C2") (pinfunction "RST_C2") (pintype "input"))
      (node (ref "U1") (pin "40") (pinfunction "SIM_RST_40") (pintype "output"))
    )
    (net (code "65") (name "TX") (class "Default")
      (node (ref "J1") (pin "13") (pinfunction "FUNC_TX_13") (pintype "bidirectional"))
      (node (ref "U2") (pin "13") (pinfunction "B2_13") (pintype "bidirectional"))
    )
    (net (code "66") (name "USB_N") (class "Default")
      (node (ref "D6") (pin "4") (pinfunction "4_4") (pintype "bidirectional"))
      (node (ref "J1") (pin "37") (pinfunction "USBHOST_D-_37") (pintype "bidirectional"))
      (node (ref "U1") (pin "28") (pinfunction "USB_D-_28") (pintype "bidirectional"))
    )
    (net (code "67") (name "USB_P") (class "Default")
      (node (ref "D6") (pin "6") (pinfunction "6_6") (pintype "bidirectional"))
      (node (ref "J1") (pin "35") (pinfunction "USBHOST_D+_35") (pintype "bidirectional"))
      (node (ref "U1") (pin "29") (pinfunction "USB_D+_29") (pintype "bidirectional"))
    )
    (net (code "68") (name "VCC") (class "Default")
      (node (ref "D2") (pin "A") (pinfunction "A_A") (pintype "passive"))
      (node (ref "J1") (pin "72") (pinfunction "VCC_72") (pintype "bidirectional"))
      (node (ref "J1") (pin "74") (pinfunction "VCC_74") (pintype "bidirectional"))
    )
    (net (code "69") (name "VCCIO") (class "Default")
      (node (ref "C17") (pin "1") (pinfunction "1_1") (pintype "passive"))
      (node (ref "D16") (pin "A") (pinfunction "A_A") (pintype "passive"))
      (node (ref "R3") (pin "2") (pinfunction "2_2") (pintype "passive"))
      (node (ref "R45") (pin "1") (pinfunction "1_1") (pintype "passive"))
      (node (ref "U1") (pin "4") (pinfunction "V_INT_4") (pintype "output"))
      (node (ref "U2") (pin "16") (pinfunction "VCCA_16") (pintype "power_in"))
      (node (ref "U2") (pin "2") (pinfunction "DIR2_2") (pintype "input"))
      (node (ref "U2") (pin "8") (pinfunction "DIR4_8") (pintype "input"))
    )
    (net (code "70") (name "VIN") (class "Default")
      (node (ref "C21") (pin "+") (pinfunction "+_+") (pintype "passive"))
      (node (ref "C23") (pin "1") (pinfunction "1_1") (pintype "passive"))
      (node (ref "C25") (pin "1") (pinfunction "1_1") (pintype "passive"))
      (node (ref "D1") (pin "C") (pinfunction "C_C") (pintype "passive"))
      (node (ref "D2") (pin "C") (pinfunction "C_C") (pintype "passive"))
      (node (ref "U3") (pin "1") (pinfunction "IN_1") (pintype "input"))
      (node (ref "U5") (pin "8") (pinfunction "IN_8") (pintype "input"))
    )
    (net (code "71") (name "VSIM") (class "Default")
      (node (ref "C36") (pin "2") (pinfunction "2_2") (pintype "passive"))
      (node (ref "C38") (pin "2") (pinfunction "2_2") (pintype "passive"))
      (node (ref "D15") (pin "3") (pinfunction "3_3") (pintype "bidirectional"))
      (node (ref "J9") (pin "C1") (pinfunction "VCC_C1") (pintype "power_in"))
      (node (ref "U1") (pin "41") (pinfunction "VSIM_41") (pintype "output"))
    )
    (net (code "72") (name "V_USB") (class "Default")
      (node (ref "D1") (pin "A") (pinfunction "A_A") (pintype "passive"))
      (node (ref "D6") (pin "5") (pinfunction "5_5") (pintype "power_in"))
      (node (ref "F2") (pin "2") (pinfunction "2_2") (pintype "bidirectional"))
      (node (ref "U1") (pin "17") (pinfunction "VUSB_DET_17") (pintype "input"))
    )
    (net (code "73") (name "unconnected-(J1-A0-Pad38)") (class "Default")
      (node (ref "J1") (pin "38") (pinfunction "A0_38") (pintype "bidirectional"))
    )
    (net (code "74") (name "unconnected-(J1-CAN-RX-Pad43)") (class "Default")
      (node (ref "J1") (pin "43") (pinfunction "CAN-RX_43") (pintype "bidirectional"))
    )
    (net (code "75") (name "unconnected-(J1-CAN-TX-Pad41)") (class "Default")
      (node (ref "J1") (pin "41") (pinfunction "CAN-TX_41") (pintype "bidirectional"))
    )
    (net (code "76") (name "unconnected-(J1-DFU_FC_RX-Pad6)") (class "Default")
      (node (ref "J1") (pin "6") (pinfunction "DFU_FC_RX_6") (pintype "bidirectional"))
    )
    (net (code "77") (name "unconnected-(J1-DFU_FC_TX-Pad4)") (class "Default")
      (node (ref "J1") (pin "4") (pinfunction "DFU_FC_TX_4") (pintype "bidirectional"))
    )
    (net (code "78") (name "unconnected-(J1-DFU_~{ACTIVE}-Pad10)") (class "Default")
      (node (ref "J1") (pin "10") (pinfunction "DFU_~{ACTIVE}_10") (pintype "bidirectional"))
    )
    (net (code "79") (name "unconnected-(J1-DFU_~{BOOT}-Pad66)") (class "Default")
      (node (ref "J1") (pin "66") (pinfunction "DFU_~{BOOT}_66") (pintype "bidirectional"))
    )
    (net (code "80") (name "unconnected-(J1-DFU_~{RST}-Pad68)") (class "Default")
      (node (ref "J1") (pin "68") (pinfunction "DFU_~{RST}_68") (pintype "bidirectional"))
    )
    (net (code "81") (name "unconnected-(J1-F3-Pad53)") (class "Default")
      (node (ref "J1") (pin "53") (pinfunction "F3_53") (pintype "bidirectional"))
    )
    (net (code "82") (name "unconnected-(J1-F4-Pad55)") (class "Default")
      (node (ref "J1") (pin "55") (pinfunction "F4_55") (pintype "bidirectional"))
    )
    (net (code "83") (name "unconnected-(J1-F6-Pad59)") (class "Default")
      (node (ref "J1") (pin "59") (pinfunction "F6_59") (pintype "bidirectional"))
    )
    (net (code "84") (name "unconnected-(J1-I2C_~{INT}-Pad23)") (class "Default")
      (node (ref "J1") (pin "23") (pinfunction "I2C_~{INT}_23") (pintype "bidirectional"))
    )
    (net (code "85") (name "unconnected-(J1-SPI_SCK-Pad3)") (class "Default")
      (node (ref "J1") (pin "3") (pinfunction "SPI_SCK_3") (pintype "bidirectional"))
    )
    (net (code "86") (name "unconnected-(J1-SPI_SDI-Pad5)") (class "Default")
      (node (ref "J1") (pin "5") (pinfunction "SPI_SDI_5") (pintype "bidirectional"))
    )
    (net (code "87") (name "unconnected-(J1-SPI_SDO-Pad7)") (class "Default")
      (node (ref "J1") (pin "7") (pinfunction "SPI_SDO_7") (pintype "bidirectional"))
    )
    (net (code "88") (name "unconnected-(J1-USB_VIN-Pad70)") (class "Default")
      (node (ref "J1") (pin "70") (pinfunction "USB_VIN_70") (pintype "bidirectional"))
    )
    (net (code "89") (name "unconnected-(J9-VPP-PadC6)") (class "Default")
      (node (ref "J9") (pin "C6") (pinfunction "VPP_C6") (pintype "input"))
    )
    (net (code "90") (name "unconnected-(U1-DCD_O-Pad8)") (class "Default")
      (node (ref "U1") (pin "8") (pinfunction "DCD_O_8") (pintype "output"))
    )
    (net (code "91") (name "unconnected-(U1-DSR_O-Pad6)") (class "Default")
      (node (ref "U1") (pin "6") (pinfunction "DSR_O_6") (pintype "output"))
    )
    (net (code "92") (name "unconnected-(U1-EXT_INT-Pad33)") (class "Default")
      (node (ref "U1") (pin "33") (pinfunction "EXT_INT_33") (pintype "input"))
    )
    (net (code "93") (name "unconnected-(U1-GPIO2-Pad23)") (class "Default")
      (node (ref "U1") (pin "23") (pinfunction "GPIO2_23") (pintype "bidirectional"))
    )
    (net (code "94") (name "unconnected-(U1-GPIO3-Pad24)") (class "Default")
      (node (ref "U1") (pin "24") (pinfunction "GPIO3_24") (pintype "bidirectional"))
    )
    (net (code "95") (name "unconnected-(U1-GPIO4-Pad25)") (class "Default")
      (node (ref "U1") (pin "25") (pinfunction "GPIO4_25") (pintype "bidirectional"))
    )
    (net (code "96") (name "unconnected-(U1-GPIO6{slash}TP-Pad19)") (class "Default")
      (node (ref "U1") (pin "19") (pinfunction "GPIO6/TP_19") (pintype "bidirectional"))
    )
    (net (code "97") (name "unconnected-(U1-I2S_CLK-Pad36)") (class "Default")
      (node (ref "U1") (pin "36") (pinfunction "I2S_CLK_36") (pintype "output"))
    )
    (net (code "98") (name "unconnected-(U1-I2S_RXD-Pad37)") (class "Default")
      (node (ref "U1") (pin "37") (pinfunction "I2S_RXD_37") (pintype "input"))
    )
    (net (code "99") (name "unconnected-(U1-I2S_TXD-Pad35)") (class "Default")
      (node (ref "U1") (pin "35") (pinfunction "I2S_TXD_35") (pintype "output"))
    )
    (net (code "100") (name "unconnected-(U1-I2S_WA-Pad34)") (class "Default")
      (node (ref "U1") (pin "34") (pinfunction "I2S_WA_34") (pintype "output"))
    )
    (net (code "101") (name "unconnected-(U1-RSVD-Pad2)") (class "Default")
      (node (ref "U1") (pin "2") (pinfunction "RSVD_2") (pintype "no_connect"))
    )
    (net (code "102") (name "unconnected-(U1-SCL-Pad27)") (class "Default")
      (node (ref "U1") (pin "27") (pinfunction "SCL_27") (pintype "bidirectional"))
    )
    (net (code "103") (name "unconnected-(U1-SDA-Pad26)") (class "Default")
      (node (ref "U1") (pin "26") (pinfunction "SDA_26") (pintype "bidirectional"))
    )
    (net (code "104") (name "unconnected-(U1-SDIO_CLK-Pad45)") (class "Default")
      (node (ref "U1") (pin "45") (pinfunction "SDIO_CLK_45") (pintype "output"))
    )
    (net (code "105") (name "unconnected-(U1-SDIO_CMD-Pad46)") (class "Default")
      (node (ref "U1") (pin "46") (pinfunction "SDIO_CMD_46") (pintype "bidirectional"))
    )
    (net (code "106") (name "unconnected-(U1-SDIO_D0-Pad47)") (class "Default")
      (node (ref "U1") (pin "47") (pinfunction "SDIO_D0_47") (pintype "bidirectional"))
    )
    (net (code "107") (name "unconnected-(U1-SDIO_D1-Pad49)") (class "Default")
      (node (ref "U1") (pin "49") (pinfunction "SDIO_D1_49") (pintype "bidirectional"))
    )
    (net (code "108") (name "unconnected-(U1-SDIO_D2-Pad44)") (class "Default")
      (node (ref "U1") (pin "44") (pinfunction "SDIO_D2_44") (pintype "bidirectional"))
    )
    (net (code "109") (name "unconnected-(U1-SDIO_D3-Pad48)") (class "Default")
      (node (ref "U1") (pin "48") (pinfunction "SDIO_D3_48") (pintype "bidirectional"))
    )
  )
)
